# bridge_bq79600.net
KiCad netlist of a schematic drawn in Altium Designer
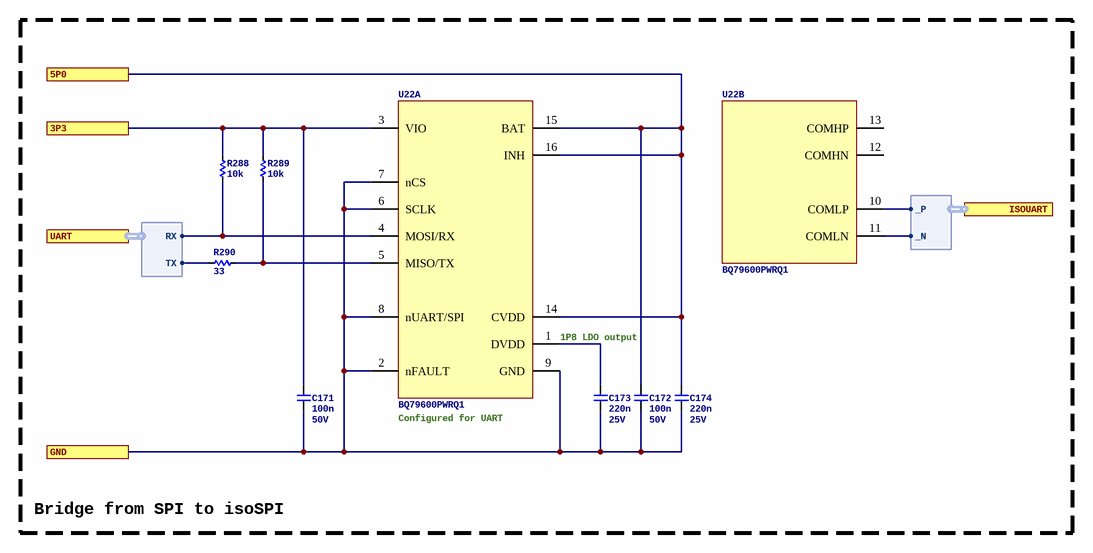
[diagram p0: bridge_bq79600.SchDoc]

(export (version "E")
  (design (tool "Eeschema 10.0.6"))
  (components
    (comp (ref "C171")
      (value "CL05B104KB54PNC")
      (footprint "C0402")
      (fields
        (field (name "CAPACITANCE") "100n")
        (field (name "MANUFACTURER") "Samsung Electro-Mechanics")
        (field (name "VOLTAGE RATING") "50V")
      )
      (libsource (lib "database") (part "__template_cap"))
    )
    (comp (ref "C172")
      (value "CL05B104KB54PNC")
      (footprint "C0402")
      (fields
        (field (name "CAPACITANCE") "100n")
        (field (name "MANUFACTURER") "Samsung Electro-Mechanics")
        (field (name "VOLTAGE RATING") "50V")
      )
      (libsource (lib "database") (part "__template_cap"))
    )
    (comp (ref "C173")
      (value "TMK105B7224KV-FR")
      (footprint "C0402")
      (fields
        (field (name "CAPACITANCE") "220n")
        (field (name "MANUFACTURER") "Taiyo Yuden")
        (field (name "VOLTAGE RATING") "25V")
      )
      (libsource (lib "database") (part "__template_cap"))
    )
    (comp (ref "C174")
      (value "TMK105B7224KV-FR")
      (footprint "C0402")
      (fields
        (field (name "CAPACITANCE") "220n")
        (field (name "MANUFACTURER") "Taiyo Yuden")
        (field (name "VOLTAGE RATING") "25V")
      )
      (libsource (lib "database") (part "__template_cap"))
    )
    (comp (ref "R288")
      (value "10k")
      (footprint "R0402")
      (fields
        (field (name "TOLERANCE") "1%")
        (field (name "MANUFACTURER PART NUMBER") "0402WGF1002TCE")
        (field (name "MANUFACTURER") "UNI-ROYAL(Uniroyal Elec)")
      )
      (libsource (lib "database") (part "__template_resistor"))
    )
    (comp (ref "R289")
      (value "10k")
      (footprint "R0402")
      (fields
        (field (name "TOLERANCE") "1%")
        (field (name "MANUFACTURER PART NUMBER") "0402WGF1002TCE")
        (field (name "MANUFACTURER") "UNI-ROYAL(Uniroyal Elec)")
      )
      (libsource (lib "database") (part "__template_resistor"))
    )
    (comp (ref "R290")
      (value "33")
      (footprint "R0402")
      (fields
        (field (name "TOLERANCE") "1%")
        (field (name "MANUFACTURER PART NUMBER") "0402WGF330JTCE")
        (field (name "MANUFACTURER") "UNI-ROYAL(Uniroyal Elec)")
      )
      (libsource (lib "database") (part "__template_resistor"))
    )
    (comp (ref "U22")
      (value "BQ79600PWRQ1")
      (footprint "TI_PW0016A")
      (description "Automotive SPI/UART communication interface functional-safety compliant with automatic host wakeup")
      (fields (field (name "MANUFACTURER") "Texas Instruments"))
      (libsource (lib "SSCP") (part "ISO_BQ79600PWRQ1"))
    )
  )
  (nets
    (net (code "3") (name "/3P3") (class "Default")
      (node (ref "C171") (pin "1") (pintype "passive"))
      (node (ref "R288") (pin "2") (pintype "passive"))
      (node (ref "R289") (pin "2") (pintype "passive"))
      (node (ref "U22") (pin "3") (pinfunction "VIO_3") (pintype "passive"))
    )
    (net (code "4") (name "/5P0") (class "Default")
      (node (ref "C172") (pin "1") (pintype "passive"))
      (node (ref "C174") (pin "1") (pintype "passive"))
      (node (ref "U22") (pin "14") (pinfunction "CVDD_14") (pintype "passive"))
      (node (ref "U22") (pin "15") (pinfunction "BAT_15") (pintype "passive"))
      (node (ref "U22") (pin "16") (pinfunction "INH_16") (pintype "passive"))
    )
    (net (code "5") (name "/GND") (class "Default")
      (node (ref "C171") (pin "2") (pintype "passive"))
      (node (ref "C172") (pin "2") (pintype "passive"))
      (node (ref "C173") (pin "2") (pintype "passive"))
      (node (ref "C174") (pin "2") (pintype "passive"))
      (node (ref "U22") (pin "2") (pinfunction "nFAULT_2") (pintype "passive"))
      (node (ref "U22") (pin "6") (pinfunction "SCLK_6") (pintype "passive"))
      (node (ref "U22") (pin "7") (pinfunction "nCS_7") (pintype "passive"))
      (node (ref "U22") (pin "8") (pinfunction "nUART/SPI_8") (pintype "passive"))
      (node (ref "U22") (pin "9") (pinfunction "GND_9") (pintype "passive"))
    )
    (net (code "6") (name "/RX") (class "Default")
      (node (ref "R288") (pin "1") (pintype "passive"))
      (node (ref "U22") (pin "4") (pinfunction "MOSI/RX_4") (pintype "passive"))
    )
    (net (code "7") (name "/TX") (class "Default") (node (ref "R290") (pin "2") (pintype "passive")))
    (net (code "8") (name "/_N") (class "Default")
      (node (ref "U22") (pin "11") (pinfunction "COMLN_11") (pintype "passive"))
    )
    (net (code "9") (name "/_P") (class "Default")
      (node (ref "U22") (pin "10") (pinfunction "COMLP_10") (pintype "passive"))
    )
    (net (code "12") (name "Net-(U22A-DVDD)") (class "Default")
      (node (ref "C173") (pin "1") (pintype "passive"))
      (node (ref "U22") (pin "1") (pinfunction "DVDD_1") (pintype "passive"))
    )
    (net (code "13") (name "Net-(U22A-MISO{slash}TX)") (class "Default")
      (node (ref "R289") (pin "1") (pintype "passive"))
      (node (ref "R290") (pin "1") (pintype "passive"))
      (node (ref "U22") (pin "5") (pinfunction "MISO/TX_5") (pintype "passive"))
    )
    (net (code "14") (name "unconnected-(U22B-COMHN-Pad12)") (class "Default")
      (node (ref "U22") (pin "12") (pinfunction "COMHN_12") (pintype "passive"))
    )
    (net (code "15") (name "unconnected-(U22B-COMHP-Pad13)") (class "Default")
      (node (ref "U22") (pin "13") (pinfunction "COMHP_13") (pintype "passive"))
    )
  )
)
